# MotorsteuerungKlein.net
KiCad netlist of a schematic drawn in EAGLE
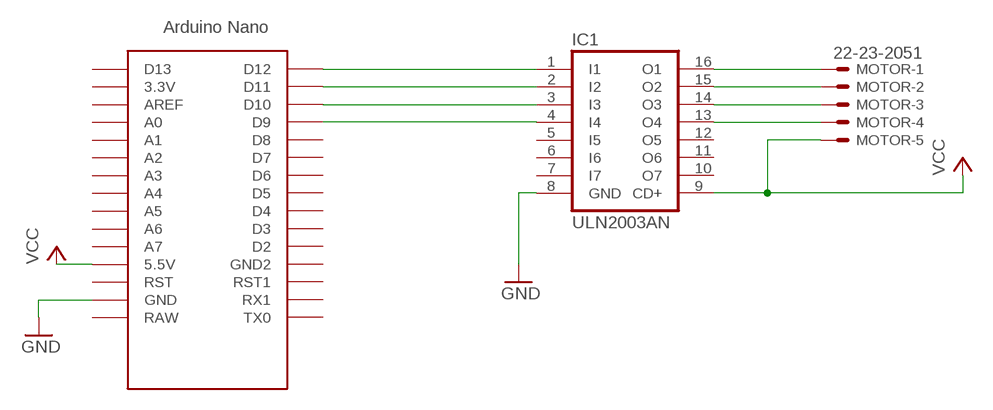
[diagram p0: schematic, sheet 1]

(export (version "E")
  (design (tool "Eeschema 10.0.6"))
  (components
    (comp (ref "IC1")
      (value "ULN2003AN")
      (footprint "eagle-import:DIL16")
      (libsource (lib "eagle-import") (part "ULN2003AN"))
    )
    (comp (ref "MOTOR")
      (value "22-23-2051")
      (footprint "eagle-import:22-23-2051")
      (fields (field (name "MF") "MOLEX"))
      (libsource (lib "eagle-import") (part "22-23-2051"))
    )
    (comp (ref "U$1")
      (value "NANO")
      (footprint "eagle-import:NANO")
      (libsource (lib "eagle-import") (part "NANO"))
    )
  )
  (nets
    (net (code "1") (name "GND") (class "Default")
      (node (ref "IC1") (pin "8") (pinfunction "GND_8") (pintype "power_in"))
      (node (ref "U$1") (pin "GND") (pinfunction "GND_GND") (pintype "bidirectional"))
    )
    (net (code "2") (name "Net-(IC1-I1)") (class "Default")
      (node (ref "IC1") (pin "1") (pinfunction "I1_1") (pintype "input"))
      (node (ref "U$1") (pin "D12") (pinfunction "D12_D12") (pintype "bidirectional"))
    )
    (net (code "3") (name "Net-(IC1-I2)") (class "Default")
      (node (ref "IC1") (pin "2") (pinfunction "I2_2") (pintype "input"))
      (node (ref "U$1") (pin "D11") (pinfunction "D11_D11") (pintype "bidirectional"))
    )
    (net (code "4") (name "Net-(IC1-I3)") (class "Default")
      (node (ref "IC1") (pin "3") (pinfunction "I3_3") (pintype "input"))
      (node (ref "U$1") (pin "D10") (pinfunction "D10_D10") (pintype "bidirectional"))
    )
    (net (code "5") (name "Net-(IC1-I4)") (class "Default")
      (node (ref "IC1") (pin "4") (pinfunction "I4_4") (pintype "input"))
      (node (ref "U$1") (pin "D9") (pinfunction "D9_D9") (pintype "bidirectional"))
    )
    (net (code "6") (name "Net-(IC1-O1)") (class "Default")
      (node (ref "IC1") (pin "16") (pinfunction "O1_16") (pintype "open_collector"))
      (node (ref "MOTOR") (pin "1") (pinfunction "S_1") (pintype "passive"))
    )
    (net (code "7") (name "Net-(IC1-O2)") (class "Default")
      (node (ref "IC1") (pin "15") (pinfunction "O2_15") (pintype "open_collector"))
      (node (ref "MOTOR") (pin "2") (pinfunction "S_2") (pintype "passive"))
    )
    (net (code "8") (name "Net-(IC1-O3)") (class "Default")
      (node (ref "IC1") (pin "14") (pinfunction "O3_14") (pintype "open_collector"))
      (node (ref "MOTOR") (pin "3") (pinfunction "S_3") (pintype "passive"))
    )
    (net (code "9") (name "Net-(IC1-O4)") (class "Default")
      (node (ref "IC1") (pin "13") (pinfunction "O4_13") (pintype "open_collector"))
      (node (ref "MOTOR") (pin "4") (pinfunction "S_4") (pintype "passive"))
    )
    (net (code "10") (name "VCC") (class "Default")
      (node (ref "IC1") (pin "9") (pinfunction "CD+_9") (pintype "passive"))
      (node (ref "MOTOR") (pin "5") (pinfunction "S_5") (pintype "passive"))
      (node (ref "U$1") (pin "5V") (pinfunction "5.5V_5V") (pintype "bidirectional"))
    )
    (net (code "11") (name "unconnected-(IC1-I5-Pad5)") (class "Default")
      (node (ref "IC1") (pin "5") (pinfunction "I5_5") (pintype "input"))
    )
    (net (code "12") (name "unconnected-(IC1-I6-Pad6)") (class "Default")
      (node (ref "IC1") (pin "6") (pinfunction "I6_6") (pintype "input"))
    )
    (net (code "13") (name "unconnected-(IC1-I7-Pad7)") (class "Default")
      (node (ref "IC1") (pin "7") (pinfunction "I7_7") (pintype "input"))
    )
    (net (code "14") (name "unconnected-(IC1-O5-Pad12)") (class "Default")
      (node (ref "IC1") (pin "12") (pinfunction "O5_12") (pintype "open_collector"))
    )
    (net (code "15") (name "unconnected-(IC1-O6-Pad11)") (class "Default")
      (node (ref "IC1") (pin "11") (pinfunction "O6_11") (pintype "open_collector"))
    )
    (net (code "16") (name "unconnected-(IC1-O7-Pad10)") (class "Default")
      (node (ref "IC1") (pin "10") (pinfunction "O7_10") (pintype "open_collector"))
    )
    (net (code "17") (name "unconnected-(U$1-GND2-PadGND1)") (class "Default")
      (node (ref "U$1") (pin "GND1") (pinfunction "GND2_GND1") (pintype "bidirectional"))
    )
    (net (code "18") (name "unconnected-(U$1-Pad3.3V)") (class "Default")
      (node (ref "U$1") (pin "3.3V") (pinfunction "3.3V_3.3V") (pintype "bidirectional"))
    )
    (net (code "19") (name "unconnected-(U$1-PadA0)") (class "Default")
      (node (ref "U$1") (pin "A0") (pinfunction "A0_A0") (pintype "bidirectional"))
    )
    (net (code "20") (name "unconnected-(U$1-PadA1)") (class "Default")
      (node (ref "U$1") (pin "A1") (pinfunction "A1_A1") (pintype "bidirectional"))
    )
    (net (code "21") (name "unconnected-(U$1-PadA2)") (class "Default")
      (node (ref "U$1") (pin "A2") (pinfunction "A2_A2") (pintype "bidirectional"))
    )
    (net (code "22") (name "unconnected-(U$1-PadA3)") (class "Default")
      (node (ref "U$1") (pin "A3") (pinfunction "A3_A3") (pintype "bidirectional"))
    )
    (net (code "23") (name "unconnected-(U$1-PadA4)") (class "Default")
      (node (ref "U$1") (pin "A4") (pinfunction "A4_A4") (pintype "bidirectional"))
    )
    (net (code "24") (name "unconnected-(U$1-PadA5)") (class "Default")
      (node (ref "U$1") (pin "A5") (pinfunction "A5_A5") (pintype "bidirectional"))
    )
    (net (code "25") (name "unconnected-(U$1-PadA6)") (class "Default")
      (node (ref "U$1") (pin "A6") (pinfunction "A6_A6") (pintype "bidirectional"))
    )
    (net (code "26") (name "unconnected-(U$1-PadA7)") (class "Default")
      (node (ref "U$1") (pin "A7") (pinfunction "A7_A7") (pintype "bidirectional"))
    )
    (net (code "27") (name "unconnected-(U$1-PadAREF)") (class "Default")
      (node (ref "U$1") (pin "AREF") (pinfunction "AREF_AREF") (pintype "bidirectional"))
    )
    (net (code "28") (name "unconnected-(U$1-PadD2)") (class "Default")
      (node (ref "U$1") (pin "D2") (pinfunction "D2_D2") (pintype "bidirectional"))
    )
    (net (code "29") (name "unconnected-(U$1-PadD3)") (class "Default")
      (node (ref "U$1") (pin "D3") (pinfunction "D3_D3") (pintype "bidirectional"))
    )
    (net (code "30") (name "unconnected-(U$1-PadD4)") (class "Default")
      (node (ref "U$1") (pin "D4") (pinfunction "D4_D4") (pintype "bidirectional"))
    )
    (net (code "31") (name "unconnected-(U$1-PadD5)") (class "Default")
      (node (ref "U$1") (pin "D5") (pinfunction "D5_D5") (pintype "bidirectional"))
    )
    (net (code "32") (name "unconnected-(U$1-PadD6)") (class "Default")
      (node (ref "U$1") (pin "D6") (pinfunction "D6_D6") (pintype "bidirectional"))
    )
    (net (code "33") (name "unconnected-(U$1-PadD7)") (class "Default")
      (node (ref "U$1") (pin "D7") (pinfunction "D7_D7") (pintype "bidirectional"))
    )
    (net (code "34") (name "unconnected-(U$1-PadD8)") (class "Default")
      (node (ref "U$1") (pin "D8") (pinfunction "D8_D8") (pintype "bidirectional"))
    )
    (net (code "35") (name "unconnected-(U$1-PadD13)") (class "Default")
      (node (ref "U$1") (pin "D13") (pinfunction "D13_D13") (pintype "bidirectional"))
    )
    (net (code "36") (name "unconnected-(U$1-PadICSP1)") (class "Default")
      (node (ref "U$1") (pin "ICSP1") (pinfunction "ICSP1_ICSP1") (pintype "bidirectional"))
    )
    (net (code "37") (name "unconnected-(U$1-PadICSP2)") (class "Default")
      (node (ref "U$1") (pin "ICSP2") (pinfunction "ICSP2_ICSP2") (pintype "bidirectional"))
    )
    (net (code "38") (name "unconnected-(U$1-PadICSP3)") (class "Default")
      (node (ref "U$1") (pin "ICSP3") (pinfunction "ICSP3_ICSP3") (pintype "bidirectional"))
    )
    (net (code "39") (name "unconnected-(U$1-PadICSP4)") (class "Default")
      (node (ref "U$1") (pin "ICSP4") (pinfunction "ICSP4_ICSP4") (pintype "bidirectional"))
    )
    (net (code "40") (name "unconnected-(U$1-PadICSP5)") (class "Default")
      (node (ref "U$1") (pin "ICSP5") (pinfunction "ICSP5_ICSP5") (pintype "bidirectional"))
    )
    (net (code "41") (name "unconnected-(U$1-PadICSP6)") (class "Default")
      (node (ref "U$1") (pin "ICSP6") (pinfunction "ICSP6_ICSP6") (pintype "bidirectional"))
    )
    (net (code "42") (name "unconnected-(U$1-PadRAW)") (class "Default")
      (node (ref "U$1") (pin "RAW") (pinfunction "RAW_RAW") (pintype "bidirectional"))
    )
    (net (code "43") (name "unconnected-(U$1-PadRST)") (class "Default")
      (node (ref "U$1") (pin "RST") (pinfunction "RST_RST") (pintype "bidirectional"))
    )
    (net (code "44") (name "unconnected-(U$1-PadRST1)") (class "Default")
      (node (ref "U$1") (pin "RST1") (pinfunction "RST1_RST1") (pintype "bidirectional"))
    )
    (net (code "45") (name "unconnected-(U$1-PadRX1)") (class "Default")
      (node (ref "U$1") (pin "RX1") (pinfunction "RX1_RX1") (pintype "bidirectional"))
    )
    (net (code "46") (name "unconnected-(U$1-PadTX0)") (class "Default")
      (node (ref "U$1") (pin "TX0") (pinfunction "TX0_TX0") (pintype "bidirectional"))
    )
  )
)
